# HB-power_v1_1.net
KiCad netlist of a schematic drawn in EAGLE
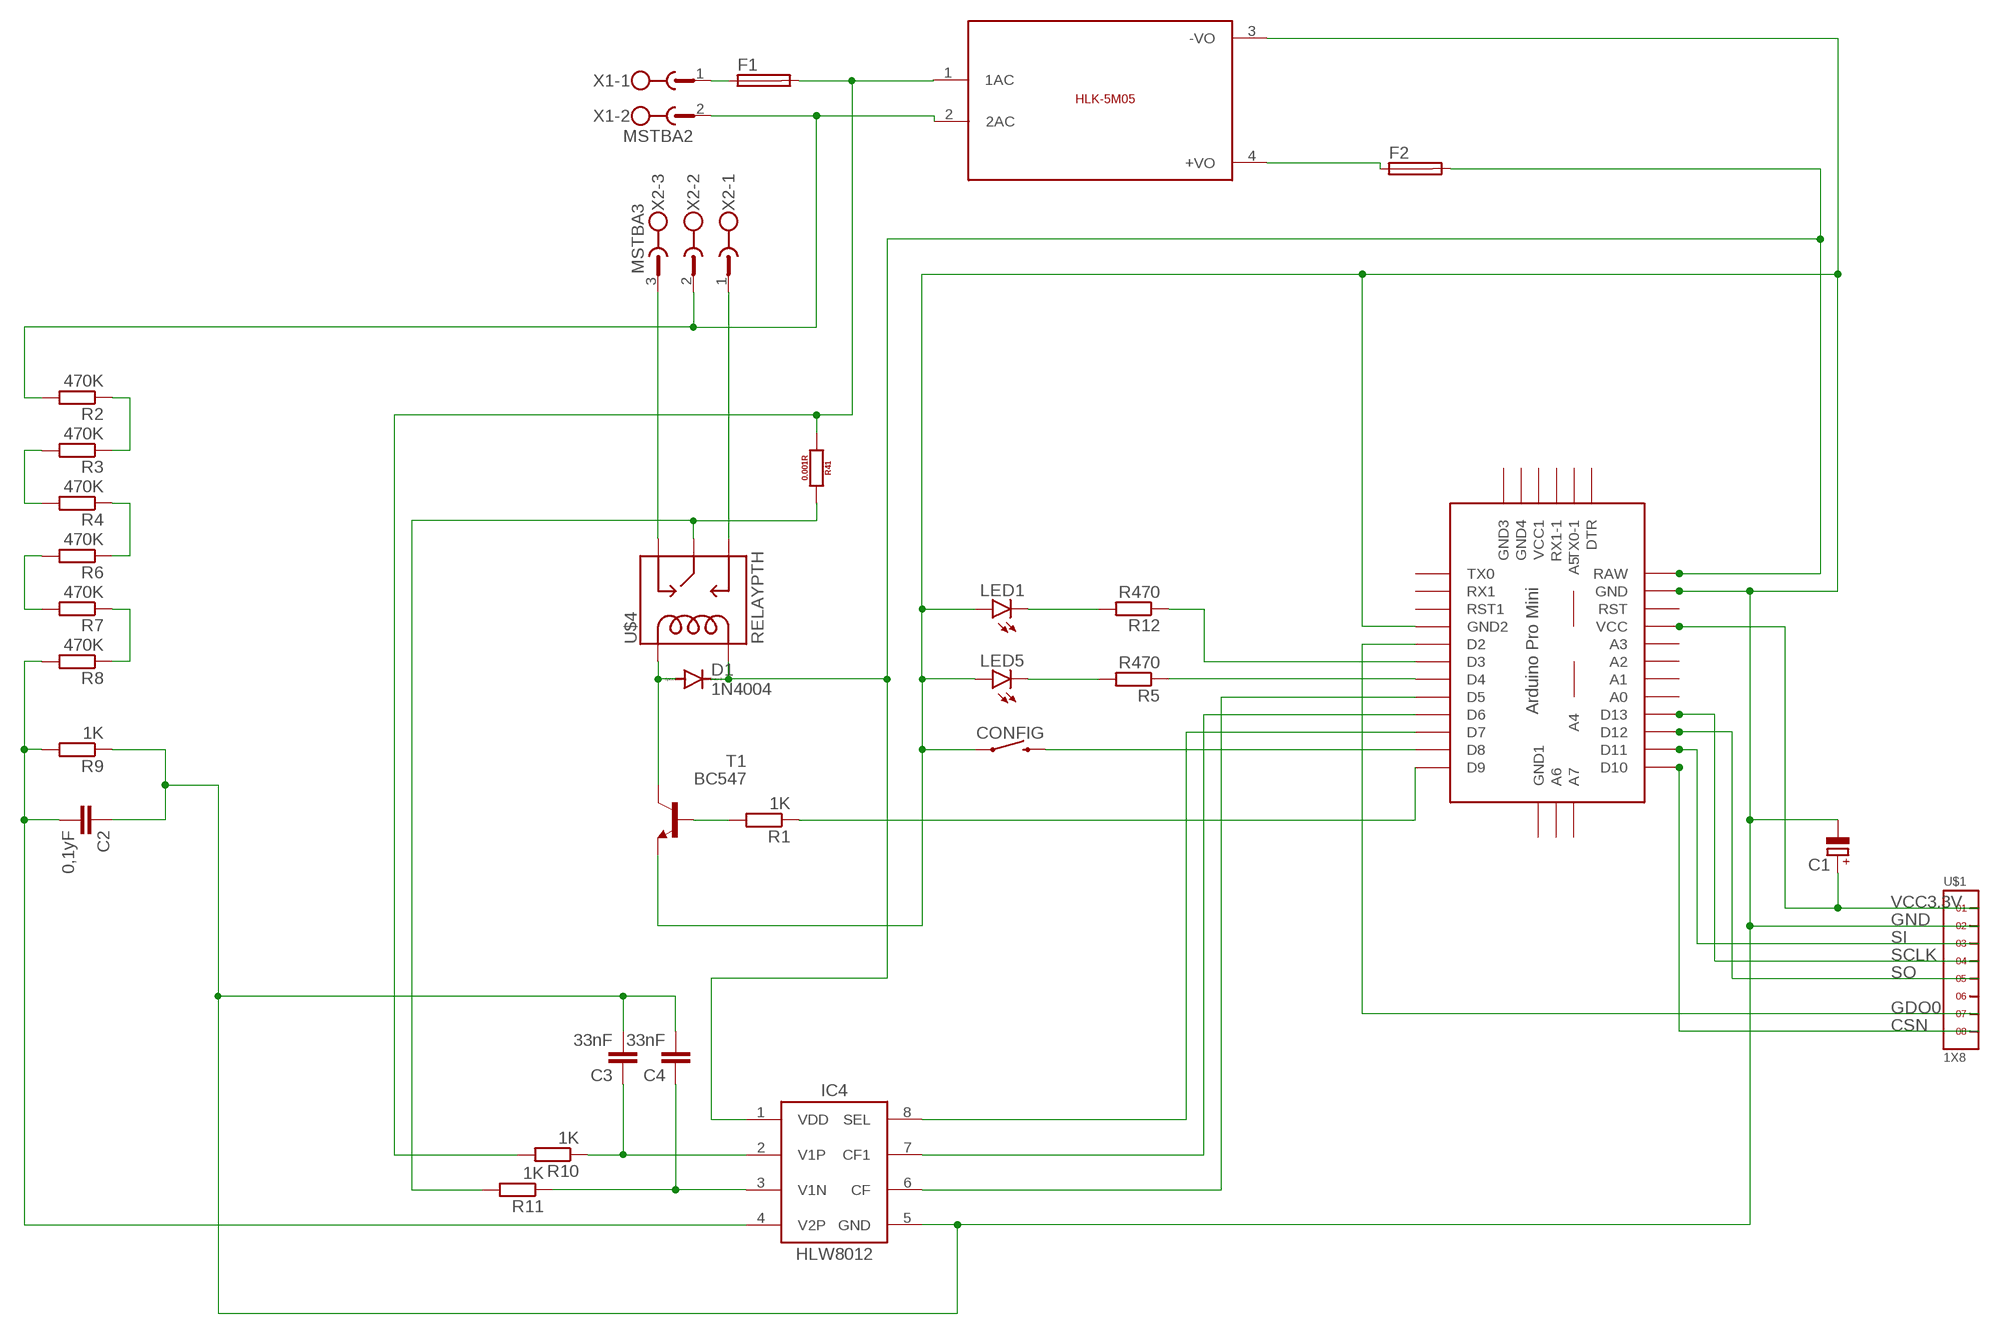
[diagram p0: schematic, sheet 1]

(export (version "E")
  (design (tool "Eeschema 10.0.6"))
  (components
    (comp (ref "C1")
      (value "CPOL-EUE2.5-5")
      (footprint "eagle-import:E2,5-5")
      (libsource (lib "eagle-import") (part "CPOL-EUE2.5-5"))
    )
    (comp (ref "C2")
      (value "0,1yF")
      (footprint "eagle-import:C050-024X044")
      (libsource (lib "eagle-import") (part "C-EU050-024X044"))
    )
    (comp (ref "C3")
      (value "33nF")
      (footprint "eagle-import:C050-024X044")
      (libsource (lib "eagle-import") (part "C-EU050-024X044"))
    )
    (comp (ref "C4")
      (value "33nF")
      (footprint "eagle-import:C050-024X044")
      (libsource (lib "eagle-import") (part "C-EU050-024X044"))
    )
    (comp (ref "CONFIG")
      (value "MOMENTARY-SWITCH-SPST-PTH-6.0MM-KIT")
      (footprint "eagle-import:TACTILE_SWITCH_PTH_6.0MM_KIT")
      (libsource (lib "eagle-import") (part "MOMENTARY-SWITCH-SPST-PTH-6.0MM-KIT"))
    )
    (comp (ref "D1")
      (value "1N4004")
      (footprint "eagle-import:DO41-10")
      (libsource (lib "eagle-import") (part "1N4004"))
    )
    (comp (ref "F1")
      (value "SH22,5A")
      (footprint "eagle-import:SH22,5A")
      (fields (field (name "MPN") "0031.7701.11"))
      (libsource (lib "eagle-import") (part "SH22,5A"))
    )
    (comp (ref "F2")
      (value "SH22,5A")
      (footprint "eagle-import:SH22,5A")
      (fields (field (name "MPN") "0031.7701.11"))
      (libsource (lib "eagle-import") (part "SH22,5A"))
    )
    (comp (ref "IC4")
      (value "HLW8012")
      (footprint "eagle-import:SOP8")
      (libsource (lib "eagle-import") (part "HLW8012"))
    )
    (comp (ref "LED1")
      (value "LED3MM")
      (footprint "eagle-import:LED3MM")
      (libsource (lib "eagle-import") (part "LED3MM"))
    )
    (comp (ref "LED5")
      (value "LED3MM")
      (footprint "eagle-import:LED3MM")
      (libsource (lib "eagle-import") (part "LED3MM"))
    )
    (comp (ref "R1")
      (value "1K")
      (footprint "eagle-import:0309_10")
      (libsource (lib "eagle-import") (part "R-EU_0309/10"))
    )
    (comp (ref "R2")
      (value "470K")
      (footprint "eagle-import:0309_10")
      (libsource (lib "eagle-import") (part "R-EU_0309/10"))
    )
    (comp (ref "R3")
      (value "470K")
      (footprint "eagle-import:0309_10")
      (libsource (lib "eagle-import") (part "R-EU_0309/10"))
    )
    (comp (ref "R4")
      (value "470K")
      (footprint "eagle-import:0309_10")
      (libsource (lib "eagle-import") (part "R-EU_0309/10"))
    )
    (comp (ref "R5")
      (value "R470")
      (footprint "eagle-import:0309_10")
      (libsource (lib "eagle-import") (part "R-EU_0309/10"))
    )
    (comp (ref "R6")
      (value "470K")
      (footprint "eagle-import:0309_10")
      (libsource (lib "eagle-import") (part "R-EU_0309/10"))
    )
    (comp (ref "R7")
      (value "470K")
      (footprint "eagle-import:0309_10")
      (libsource (lib "eagle-import") (part "R-EU_0309/10"))
    )
    (comp (ref "R8")
      (value "470K")
      (footprint "eagle-import:0309_10")
      (libsource (lib "eagle-import") (part "R-EU_0309/10"))
    )
    (comp (ref "R9")
      (value "1K")
      (footprint "eagle-import:0309_10")
      (libsource (lib "eagle-import") (part "R-EU_0309/10"))
    )
    (comp (ref "R10")
      (value "1K")
      (footprint "eagle-import:0309_10")
      (libsource (lib "eagle-import") (part "R-EU_0309/10"))
    )
    (comp (ref "R11")
      (value "1K")
      (footprint "eagle-import:0309_10")
      (libsource (lib "eagle-import") (part "R-EU_0309/10"))
    )
    (comp (ref "R12")
      (value "R470")
      (footprint "eagle-import:0309_10")
      (libsource (lib "eagle-import") (part "R-EU_0309/10"))
    )
    (comp (ref "R41")
      (value "0.001R")
      (footprint "eagle-import:2512")
      (libsource (lib "eagle-import") (part "RESISTOR2512"))
    )
    (comp (ref "T1")
      (value "BC547")
      (footprint "eagle-import:TO92")
      (libsource (lib "eagle-import") (part "BC547"))
    )
    (comp (ref "U$1")
      (value "1X8")
      (footprint "eagle-import:1X8")
      (libsource (lib "eagle-import") (part "1X8"))
    )
    (comp (ref "U$2")
      (value "ABK-PRO-MINI")
      (footprint "eagle-import:ABK-PRO-MINI")
      (libsource (lib "eagle-import") (part "ABK-PRO-MINI"))
    )
    (comp (ref "U$3")
      (value "5VDC/5W")
      (footprint "eagle-import:HLK-5M05")
      (libsource (lib "eagle-import") (part "HLK-5M05"))
    )
    (comp (ref "U$4")
      (value "RELAYPTH")
      (footprint "eagle-import:SRD-05VDC-SL-C")
      (libsource (lib "eagle-import") (part "RELAYPTH"))
    )
    (comp (ref "X1")
      (value "MSTBA2")
      (footprint "eagle-import:MSTBA2")
      (fields (field (name "MF") "FARNELL") (field (name "MPN") "1757242"))
      (libsource (lib "eagle-import") (part "MSTBA2"))
    )
    (comp (ref "X2")
      (value "MSTBA3")
      (footprint "eagle-import:MSTBA3")
      (fields (field (name "MF") "FARNELL") (field (name "MPN") "1757255"))
      (libsource (lib "eagle-import") (part "MSTBA3"))
    )
  )
  (nets
    (net (code "1") (name "/CSN") (class "Default")
      (node (ref "U$1") (pin "8") (pinfunction "8_8") (pintype "bidirectional"))
      (node (ref "U$2") (pin "D10") (pinfunction "D10_D10") (pintype "bidirectional"))
    )
    (net (code "2") (name "/GDO0") (class "Default")
      (node (ref "U$1") (pin "7") (pinfunction "7_7") (pintype "bidirectional"))
      (node (ref "U$2") (pin "D2") (pinfunction "D2_D2") (pintype "bidirectional"))
    )
    (net (code "3") (name "/GND") (class "Default")
      (node (ref "C1") (pin "-") (pinfunction "-_-") (pintype "passive"))
      (node (ref "C2") (pin "1") (pinfunction "1_1") (pintype "passive"))
      (node (ref "C3") (pin "2") (pinfunction "2_2") (pintype "passive"))
      (node (ref "C4") (pin "2") (pinfunction "2_2") (pintype "passive"))
      (node (ref "CONFIG") (pin "1") (pinfunction "1_1") (pintype "passive"))
      (node (ref "IC4") (pin "5") (pinfunction "GND_5") (pintype "power_in"))
      (node (ref "LED1") (pin "A") (pinfunction "A_A") (pintype "passive"))
      (node (ref "LED5") (pin "A") (pinfunction "A_A") (pintype "passive"))
      (node (ref "R9") (pin "1") (pinfunction "1_1") (pintype "passive"))
      (node (ref "T1") (pin "1") (pinfunction "E_1") (pintype "passive"))
      (node (ref "U$1") (pin "2") (pinfunction "2_2") (pintype "bidirectional"))
      (node (ref "U$2") (pin "GND") (pinfunction "GND_GND") (pintype "bidirectional"))
      (node (ref "U$2") (pin "GND1") (pinfunction "GND2_GND1") (pintype "bidirectional"))
      (node (ref "U$3") (pin "3") (pinfunction "-VO_3") (pintype "bidirectional"))
    )
    (net (code "4") (name "/SCLK") (class "Default")
      (node (ref "U$1") (pin "4") (pinfunction "4_4") (pintype "bidirectional"))
      (node (ref "U$2") (pin "D13") (pinfunction "D13_D13") (pintype "bidirectional"))
    )
    (net (code "5") (name "/SI") (class "Default")
      (node (ref "U$1") (pin "3") (pinfunction "3_3") (pintype "bidirectional"))
      (node (ref "U$2") (pin "D11") (pinfunction "D11_D11") (pintype "bidirectional"))
    )
    (net (code "6") (name "/SO") (class "Default")
      (node (ref "U$1") (pin "5") (pinfunction "5_5") (pintype "bidirectional"))
      (node (ref "U$2") (pin "D12") (pinfunction "D12_D12") (pintype "bidirectional"))
    )
    (net (code "7") (name "/VCC3.3V") (class "Default")
      (node (ref "C1") (pin "+") (pinfunction "+_+") (pintype "passive"))
      (node (ref "U$1") (pin "1") (pinfunction "1_1") (pintype "bidirectional"))
      (node (ref "U$2") (pin "VCC") (pinfunction "VCC_VCC") (pintype "bidirectional"))
    )
    (net (code "8") (name "Net-(CONFIG-2)") (class "Default")
      (node (ref "CONFIG") (pin "3") (pinfunction "2_3") (pintype "passive"))
      (node (ref "U$2") (pin "D8") (pinfunction "D8_D8") (pintype "bidirectional"))
    )
    (net (code "9") (name "Net-(F1-Pad1)") (class "Default")
      (node (ref "F1") (pin "1") (pinfunction "1_1") (pintype "passive"))
      (node (ref "X1") (pin "1") (pinfunction "1_1") (pintype "passive"))
    )
    (net (code "10") (name "Net-(IC4-CF)") (class "Default")
      (node (ref "IC4") (pin "6") (pinfunction "CF_6") (pintype "output"))
      (node (ref "U$2") (pin "D5") (pinfunction "D5_D5") (pintype "bidirectional"))
    )
    (net (code "11") (name "Net-(IC4-CF1)") (class "Default")
      (node (ref "IC4") (pin "7") (pinfunction "CF1_7") (pintype "output"))
      (node (ref "U$2") (pin "D6") (pinfunction "D6_D6") (pintype "bidirectional"))
    )
    (net (code "12") (name "Net-(IC4-SEL)") (class "Default")
      (node (ref "IC4") (pin "8") (pinfunction "SEL_8") (pintype "input"))
      (node (ref "U$2") (pin "D7") (pinfunction "D7_D7") (pintype "bidirectional"))
    )
    (net (code "13") (name "Net-(IC4-V1N)") (class "Default")
      (node (ref "C4") (pin "1") (pinfunction "1_1") (pintype "passive"))
      (node (ref "IC4") (pin "3") (pinfunction "V1N_3") (pintype "input"))
      (node (ref "R11") (pin "1") (pinfunction "1_1") (pintype "passive"))
    )
    (net (code "14") (name "Net-(IC4-V1P)") (class "Default")
      (node (ref "C3") (pin "1") (pinfunction "1_1") (pintype "passive"))
      (node (ref "IC4") (pin "2") (pinfunction "V1P_2") (pintype "input"))
      (node (ref "R10") (pin "1") (pinfunction "1_1") (pintype "passive"))
    )
    (net (code "15") (name "Net-(IC4-V2P)") (class "Default")
      (node (ref "C2") (pin "2") (pinfunction "2_2") (pintype "passive"))
      (node (ref "IC4") (pin "4") (pinfunction "V2P_4") (pintype "input"))
      (node (ref "R8") (pin "2") (pinfunction "2_2") (pintype "passive"))
      (node (ref "R9") (pin "2") (pinfunction "2_2") (pintype "passive"))
    )
    (net (code "16") (name "Net-(IC4-VDD)") (class "Default")
      (node (ref "D1") (pin "C") (pinfunction "C_C") (pintype "passive"))
      (node (ref "F2") (pin "2") (pinfunction "2_2") (pintype "passive"))
      (node (ref "IC4") (pin "1") (pinfunction "VDD_1") (pintype "power_in"))
      (node (ref "U$2") (pin "RAW") (pinfunction "RAW_RAW") (pintype "bidirectional"))
      (node (ref "U$4") (pin "COIL0") (pinfunction "COIL0_COIL0") (pintype "bidirectional"))
    )
    (net (code "17") (name "Net-(LED1-C)") (class "Default")
      (node (ref "LED1") (pin "K") (pinfunction "C_K") (pintype "passive"))
      (node (ref "R12") (pin "2") (pinfunction "2_2") (pintype "passive"))
    )
    (net (code "18") (name "Net-(LED5-C)") (class "Default")
      (node (ref "LED5") (pin "K") (pinfunction "C_K") (pintype "passive"))
      (node (ref "R5") (pin "2") (pinfunction "2_2") (pintype "passive"))
    )
    (net (code "19") (name "Net-(R1-Pad1)") (class "Default")
      (node (ref "R1") (pin "1") (pinfunction "1_1") (pintype "passive"))
      (node (ref "U$2") (pin "D9") (pinfunction "D9_D9") (pintype "bidirectional"))
    )
    (net (code "20") (name "Net-(R2-Pad1)") (class "Default")
      (node (ref "R2") (pin "1") (pinfunction "1_1") (pintype "passive"))
      (node (ref "R3") (pin "1") (pinfunction "1_1") (pintype "passive"))
    )
    (net (code "21") (name "Net-(R3-Pad2)") (class "Default")
      (node (ref "R3") (pin "2") (pinfunction "2_2") (pintype "passive"))
      (node (ref "R4") (pin "2") (pinfunction "2_2") (pintype "passive"))
    )
    (net (code "22") (name "Net-(R4-Pad1)") (class "Default")
      (node (ref "R4") (pin "1") (pinfunction "1_1") (pintype "passive"))
      (node (ref "R6") (pin "1") (pinfunction "1_1") (pintype "passive"))
    )
    (net (code "23") (name "Net-(R5-Pad1)") (class "Default")
      (node (ref "R5") (pin "1") (pinfunction "1_1") (pintype "passive"))
      (node (ref "U$2") (pin "D4") (pinfunction "D4_D4") (pintype "bidirectional"))
    )
    (net (code "24") (name "Net-(R6-Pad2)") (class "Default")
      (node (ref "R6") (pin "2") (pinfunction "2_2") (pintype "passive"))
      (node (ref "R7") (pin "2") (pinfunction "2_2") (pintype "passive"))
    )
    (net (code "25") (name "Net-(R7-Pad1)") (class "Default")
      (node (ref "R7") (pin "1") (pinfunction "1_1") (pintype "passive"))
      (node (ref "R8") (pin "1") (pinfunction "1_1") (pintype "passive"))
    )
    (net (code "26") (name "Net-(R11-Pad2)") (class "Default")
      (node (ref "R11") (pin "2") (pinfunction "2_2") (pintype "passive"))
      (node (ref "R41") (pin "2") (pinfunction "2_2") (pintype "passive"))
      (node (ref "U$4") (pin "SWCOMMON") (pinfunction "SWCOMMON_SWCOMMON") (pintype "bidirectional"))
    )
    (net (code "27") (name "Net-(R12-Pad1)") (class "Default")
      (node (ref "R12") (pin "1") (pinfunction "1_1") (pintype "passive"))
      (node (ref "U$2") (pin "D3") (pinfunction "D3_D3") (pintype "bidirectional"))
    )
    (net (code "28") (name "Net-(T1-B)") (class "Default")
      (node (ref "R1") (pin "2") (pinfunction "2_2") (pintype "passive"))
      (node (ref "T1") (pin "2") (pinfunction "B_2") (pintype "passive"))
    )
    (net (code "29") (name "Net-(T1-C)") (class "Default")
      (node (ref "D1") (pin "A") (pinfunction "A_A") (pintype "passive"))
      (node (ref "T1") (pin "3") (pinfunction "C_3") (pintype "passive"))
      (node (ref "U$4") (pin "COIL1") (pinfunction "COIL1_COIL1") (pintype "bidirectional"))
    )
    (net (code "30") (name "Net-(U$3-+VO)") (class "Default")
      (node (ref "F2") (pin "1") (pinfunction "1_1") (pintype "passive"))
      (node (ref "U$3") (pin "4") (pinfunction "+VO_4") (pintype "bidirectional"))
    )
    (net (code "31") (name "Net-(U$3-1AC)") (class "Default")
      (node (ref "F1") (pin "2") (pinfunction "2_2") (pintype "passive"))
      (node (ref "R10") (pin "2") (pinfunction "2_2") (pintype "passive"))
      (node (ref "R41") (pin "1") (pinfunction "1_1") (pintype "passive"))
      (node (ref "U$3") (pin "1") (pinfunction "1AC_1") (pintype "bidirectional"))
    )
    (net (code "32") (name "Net-(U$3-2AC)") (class "Default")
      (node (ref "R2") (pin "2") (pinfunction "2_2") (pintype "passive"))
      (node (ref "U$3") (pin "2") (pinfunction "2AC_2") (pintype "bidirectional"))
      (node (ref "X1") (pin "2") (pinfunction "1_2") (pintype "passive"))
      (node (ref "X2") (pin "2") (pinfunction "1_2") (pintype "passive"))
    )
    (net (code "33") (name "Net-(U$4-PadSWOPEN)") (class "Default")
      (node (ref "U$4") (pin "SWOPEN") (pinfunction "SWOPEN_SWOPEN") (pintype "bidirectional"))
      (node (ref "X2") (pin "1") (pinfunction "1_1") (pintype "passive"))
    )
    (net (code "34") (name "Net-(U$4-SWCLOSE)") (class "Default")
      (node (ref "U$4") (pin "SWCLOSED") (pinfunction "SWCLOSE_SWCLOSED") (pintype "bidirectional"))
      (node (ref "X2") (pin "3") (pinfunction "1_3") (pintype "passive"))
    )
    (net (code "35") (name "unconnected-(U$1-Pad6)") (class "Default")
      (node (ref "U$1") (pin "6") (pinfunction "6_6") (pintype "bidirectional"))
    )
    (net (code "36") (name "unconnected-(U$2-GND1-PadGND4)") (class "Default")
      (node (ref "U$2") (pin "GND4") (pinfunction "GND1_GND4") (pintype "bidirectional"))
    )
    (net (code "37") (name "unconnected-(U$2-GND3-PadGND2)") (class "Default")
      (node (ref "U$2") (pin "GND2") (pinfunction "GND3_GND2") (pintype "bidirectional"))
    )
    (net (code "38") (name "unconnected-(U$2-GND4-PadGND3)") (class "Default")
      (node (ref "U$2") (pin "GND3") (pinfunction "GND4_GND3") (pintype "bidirectional"))
    )
    (net (code "39") (name "unconnected-(U$2-PadA0)") (class "Default")
      (node (ref "U$2") (pin "A0") (pinfunction "A0_A0") (pintype "bidirectional"))
    )
    (net (code "40") (name "unconnected-(U$2-PadA1)") (class "Default")
      (node (ref "U$2") (pin "A1") (pinfunction "A1_A1") (pintype "bidirectional"))
    )
    (net (code "41") (name "unconnected-(U$2-PadA2)") (class "Default")
      (node (ref "U$2") (pin "A2") (pinfunction "A2_A2") (pintype "bidirectional"))
    )
    (net (code "42") (name "unconnected-(U$2-PadA3)") (class "Default")
      (node (ref "U$2") (pin "A3") (pinfunction "A3_A3") (pintype "bidirectional"))
    )
    (net (code "43") (name "unconnected-(U$2-PadA4)") (class "Default")
      (node (ref "U$2") (pin "A4") (pinfunction "A4_A4") (pintype "bidirectional"))
    )
    (net (code "44") (name "unconnected-(U$2-PadA5)") (class "Default")
      (node (ref "U$2") (pin "A5") (pinfunction "A5_A5") (pintype "bidirectional"))
    )
    (net (code "45") (name "unconnected-(U$2-PadA6)") (class "Default")
      (node (ref "U$2") (pin "A6") (pinfunction "A6_A6") (pintype "bidirectional"))
    )
    (net (code "46") (name "unconnected-(U$2-PadA7)") (class "Default")
      (node (ref "U$2") (pin "A7") (pinfunction "A7_A7") (pintype "bidirectional"))
    )
    (net (code "47") (name "unconnected-(U$2-PadDTR)") (class "Default")
      (node (ref "U$2") (pin "DTR") (pinfunction "DTR_DTR") (pintype "bidirectional"))
    )
    (net (code "48") (name "unconnected-(U$2-PadRST)") (class "Default")
      (node (ref "U$2") (pin "RST") (pinfunction "RST_RST") (pintype "bidirectional"))
    )
    (net (code "49") (name "unconnected-(U$2-PadRST1)") (class "Default")
      (node (ref "U$2") (pin "RST1") (pinfunction "RST1_RST1") (pintype "bidirectional"))
    )
    (net (code "50") (name "unconnected-(U$2-PadRX1)") (class "Default")
      (node (ref "U$2") (pin "RX1") (pinfunction "RX1_RX1") (pintype "bidirectional"))
    )
    (net (code "51") (name "unconnected-(U$2-PadRX1-1)") (class "Default")
      (node (ref "U$2") (pin "RX1-1") (pinfunction "RX1-1_RX1-1") (pintype "bidirectional"))
    )
    (net (code "52") (name "unconnected-(U$2-PadTX0)") (class "Default")
      (node (ref "U$2") (pin "TX0") (pinfunction "TX0_TX0") (pintype "bidirectional"))
    )
    (net (code "53") (name "unconnected-(U$2-PadTX0-1)") (class "Default")
      (node (ref "U$2") (pin "TX0-1") (pinfunction "TX0-1_TX0-1") (pintype "bidirectional"))
    )
    (net (code "54") (name "unconnected-(U$2-PadVCC1)") (class "Default")
      (node (ref "U$2") (pin "VCC1") (pinfunction "VCC1_VCC1") (pintype "bidirectional"))
    )
  )
)
